# time-shift-r1.net
KiCad netlist of a schematic drawn in EAGLE
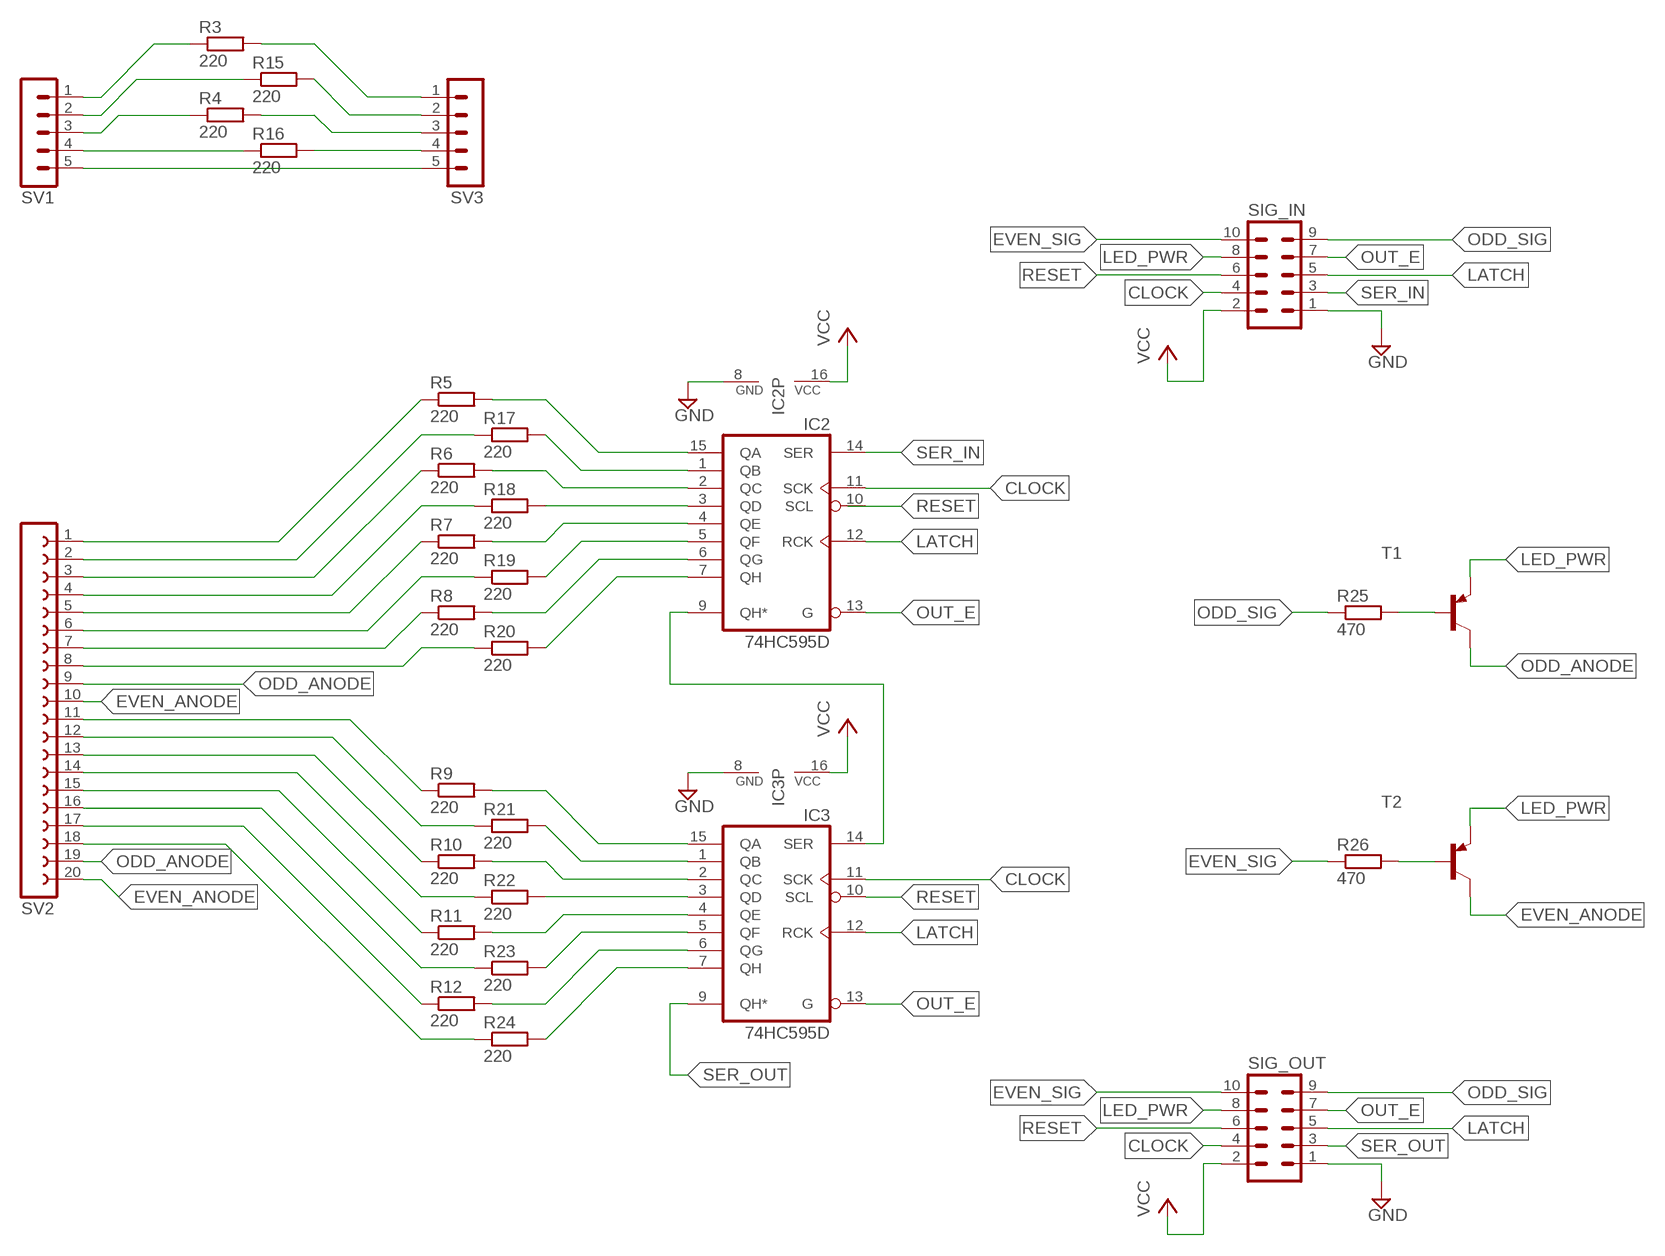
[diagram p0: schematic, sheet 1]

(export (version "E")
  (design (tool "Eeschema 10.0.6"))
  (components
    (comp (ref "IC2")
      (value "74HC595D")
      (footprint "eagle-import:SO16")
      (libsource (lib "eagle-import") (part "74595DHC"))
    )
    (comp (ref "IC3")
      (value "74HC595D")
      (footprint "eagle-import:SO16")
      (libsource (lib "eagle-import") (part "74595DHC"))
    )
    (comp (ref "R3")
      (value "220")
      (footprint "eagle-import:R0805")
      (libsource (lib "eagle-import") (part "R-EU_R0805"))
    )
    (comp (ref "R4")
      (value "220")
      (footprint "eagle-import:R0805")
      (libsource (lib "eagle-import") (part "R-EU_R0805"))
    )
    (comp (ref "R5")
      (value "220")
      (footprint "eagle-import:R0805")
      (libsource (lib "eagle-import") (part "R-EU_R0805"))
    )
    (comp (ref "R6")
      (value "220")
      (footprint "eagle-import:R0805")
      (libsource (lib "eagle-import") (part "R-EU_R0805"))
    )
    (comp (ref "R7")
      (value "220")
      (footprint "eagle-import:R0805")
      (libsource (lib "eagle-import") (part "R-EU_R0805"))
    )
    (comp (ref "R8")
      (value "220")
      (footprint "eagle-import:R0805")
      (libsource (lib "eagle-import") (part "R-EU_R0805"))
    )
    (comp (ref "R9")
      (value "220")
      (footprint "eagle-import:R0805")
      (libsource (lib "eagle-import") (part "R-EU_R0805"))
    )
    (comp (ref "R10")
      (value "220")
      (footprint "eagle-import:R0805")
      (libsource (lib "eagle-import") (part "R-EU_R0805"))
    )
    (comp (ref "R11")
      (value "220")
      (footprint "eagle-import:R0805")
      (libsource (lib "eagle-import") (part "R-EU_R0805"))
    )
    (comp (ref "R12")
      (value "220")
      (footprint "eagle-import:R0805")
      (libsource (lib "eagle-import") (part "R-EU_R0805"))
    )
    (comp (ref "R15")
      (value "220")
      (footprint "eagle-import:R0805")
      (libsource (lib "eagle-import") (part "R-EU_R0805"))
    )
    (comp (ref "R16")
      (value "220")
      (footprint "eagle-import:R0805")
      (libsource (lib "eagle-import") (part "R-EU_R0805"))
    )
    (comp (ref "R17")
      (value "220")
      (footprint "eagle-import:R0805")
      (libsource (lib "eagle-import") (part "R-EU_R0805"))
    )
    (comp (ref "R18")
      (value "220")
      (footprint "eagle-import:R0805")
      (libsource (lib "eagle-import") (part "R-EU_R0805"))
    )
    (comp (ref "R19")
      (value "220")
      (footprint "eagle-import:R0805")
      (libsource (lib "eagle-import") (part "R-EU_R0805"))
    )
    (comp (ref "R20")
      (value "220")
      (footprint "eagle-import:R0805")
      (libsource (lib "eagle-import") (part "R-EU_R0805"))
    )
    (comp (ref "R21")
      (value "220")
      (footprint "eagle-import:R0805")
      (libsource (lib "eagle-import") (part "R-EU_R0805"))
    )
    (comp (ref "R22")
      (value "220")
      (footprint "eagle-import:R0805")
      (libsource (lib "eagle-import") (part "R-EU_R0805"))
    )
    (comp (ref "R23")
      (value "220")
      (footprint "eagle-import:R0805")
      (libsource (lib "eagle-import") (part "R-EU_R0805"))
    )
    (comp (ref "R24")
      (value "220")
      (footprint "eagle-import:R0805")
      (libsource (lib "eagle-import") (part "R-EU_R0805"))
    )
    (comp (ref "R25")
      (value "470")
      (footprint "eagle-import:R0805")
      (libsource (lib "eagle-import") (part "R-EU_R0805"))
    )
    (comp (ref "R26")
      (value "470")
      (footprint "eagle-import:R0805")
      (libsource (lib "eagle-import") (part "R-EU_R0805"))
    )
    (comp (ref "SIG_IN")
      (value "MA05-2")
      (footprint "eagle-import:MA05-2")
      (libsource (lib "eagle-import") (part "MA05-2"))
    )
    (comp (ref "SIG_OUT")
      (value "MA05-2")
      (footprint "eagle-import:MA05-2")
      (libsource (lib "eagle-import") (part "MA05-2"))
    )
    (comp (ref "SV1")
      (value "MA05-1")
      (footprint "eagle-import:MA05-1")
      (libsource (lib "eagle-import") (part "MA05-1"))
    )
    (comp (ref "SV2")
      (value "FE20-1")
      (footprint "eagle-import:FE20")
      (libsource (lib "eagle-import") (part "FE20-1"))
    )
    (comp (ref "SV3")
      (value "MA05-1")
      (footprint "eagle-import:MA05-1")
      (libsource (lib "eagle-import") (part "MA05-1"))
    )
    (comp (ref "T1")
      (value "BC557B-PNP-TO92-EBC")
      (footprint "eagle-import:TO92-EBC")
      (libsource (lib "eagle-import") (part "-PNP-TO92-EBCBC557B"))
    )
    (comp (ref "T2")
      (value "BC557B-PNP-TO92-EBC")
      (footprint "eagle-import:TO92-EBC")
      (libsource (lib "eagle-import") (part "-PNP-TO92-EBCBC557B"))
    )
  )
  (nets
    (net (code "1") (name "CLOCK") (class "Default")
      (node (ref "IC2") (pin "11") (pinfunction "SCK_11") (pintype "input"))
      (node (ref "IC3") (pin "11") (pinfunction "SCK_11") (pintype "input"))
      (node (ref "SIG_IN") (pin "4") (pinfunction "4_4") (pintype "passive"))
      (node (ref "SIG_OUT") (pin "4") (pinfunction "4_4") (pintype "passive"))
    )
    (net (code "2") (name "EVEN_ANODE") (class "Default")
      (node (ref "SV2") (pin "10") (pinfunction "10_10") (pintype "passive"))
      (node (ref "SV2") (pin "20") (pinfunction "20_20") (pintype "passive"))
      (node (ref "T2") (pin "C") (pinfunction "C_C") (pintype "passive"))
    )
    (net (code "3") (name "EVEN_SIG") (class "Default")
      (node (ref "R26") (pin "1") (pinfunction "1_1") (pintype "passive"))
      (node (ref "SIG_IN") (pin "10") (pinfunction "10_10") (pintype "passive"))
      (node (ref "SIG_OUT") (pin "10") (pinfunction "10_10") (pintype "passive"))
    )
    (net (code "4") (name "GND") (class "Default")
      (node (ref "IC2") (pin "8") (pinfunction "GND_8") (pintype "power_in"))
      (node (ref "IC3") (pin "8") (pinfunction "GND_8") (pintype "power_in"))
      (node (ref "SIG_IN") (pin "1") (pinfunction "1_1") (pintype "passive"))
      (node (ref "SIG_OUT") (pin "1") (pinfunction "1_1") (pintype "passive"))
    )
    (net (code "5") (name "LATCH") (class "Default")
      (node (ref "IC2") (pin "12") (pinfunction "RCK_12") (pintype "input"))
      (node (ref "IC3") (pin "12") (pinfunction "RCK_12") (pintype "input"))
      (node (ref "SIG_IN") (pin "5") (pinfunction "5_5") (pintype "passive"))
      (node (ref "SIG_OUT") (pin "5") (pinfunction "5_5") (pintype "passive"))
    )
    (net (code "6") (name "LED_PWR") (class "Default")
      (node (ref "SIG_IN") (pin "8") (pinfunction "8_8") (pintype "passive"))
      (node (ref "SIG_OUT") (pin "8") (pinfunction "8_8") (pintype "passive"))
      (node (ref "T1") (pin "E") (pinfunction "E_E") (pintype "passive"))
      (node (ref "T2") (pin "E") (pinfunction "E_E") (pintype "passive"))
    )
    (net (code "7") (name "Net-(IC2A-QA)") (class "Default")
      (node (ref "IC2") (pin "15") (pinfunction "QA_15") (pintype "tri_state"))
      (node (ref "R5") (pin "2") (pinfunction "2_2") (pintype "passive"))
    )
    (net (code "8") (name "Net-(IC2A-QB)") (class "Default")
      (node (ref "IC2") (pin "1") (pinfunction "QB_1") (pintype "tri_state"))
      (node (ref "R17") (pin "2") (pinfunction "2_2") (pintype "passive"))
    )
    (net (code "9") (name "Net-(IC2A-QC)") (class "Default")
      (node (ref "IC2") (pin "2") (pinfunction "QC_2") (pintype "tri_state"))
      (node (ref "R6") (pin "2") (pinfunction "2_2") (pintype "passive"))
    )
    (net (code "10") (name "Net-(IC2A-QD)") (class "Default")
      (node (ref "IC2") (pin "3") (pinfunction "QD_3") (pintype "tri_state"))
      (node (ref "R18") (pin "2") (pinfunction "2_2") (pintype "passive"))
    )
    (net (code "11") (name "Net-(IC2A-QE)") (class "Default")
      (node (ref "IC2") (pin "4") (pinfunction "QE_4") (pintype "tri_state"))
      (node (ref "R7") (pin "2") (pinfunction "2_2") (pintype "passive"))
    )
    (net (code "12") (name "Net-(IC2A-QF)") (class "Default")
      (node (ref "IC2") (pin "5") (pinfunction "QF_5") (pintype "tri_state"))
      (node (ref "R19") (pin "2") (pinfunction "2_2") (pintype "passive"))
    )
    (net (code "13") (name "Net-(IC2A-QG)") (class "Default")
      (node (ref "IC2") (pin "6") (pinfunction "QG_6") (pintype "tri_state"))
      (node (ref "R8") (pin "2") (pinfunction "2_2") (pintype "passive"))
    )
    (net (code "14") (name "Net-(IC2A-QH)") (class "Default")
      (node (ref "IC2") (pin "7") (pinfunction "QH_7") (pintype "tri_state"))
      (node (ref "R20") (pin "2") (pinfunction "2_2") (pintype "passive"))
    )
    (net (code "15") (name "Net-(IC2A-QH*)") (class "Default")
      (node (ref "IC2") (pin "9") (pinfunction "QH*_9") (pintype "tri_state"))
      (node (ref "IC3") (pin "14") (pinfunction "SER_14") (pintype "input"))
    )
    (net (code "16") (name "Net-(IC3A-QA)") (class "Default")
      (node (ref "IC3") (pin "15") (pinfunction "QA_15") (pintype "tri_state"))
      (node (ref "R9") (pin "2") (pinfunction "2_2") (pintype "passive"))
    )
    (net (code "17") (name "Net-(IC3A-QB)") (class "Default")
      (node (ref "IC3") (pin "1") (pinfunction "QB_1") (pintype "tri_state"))
      (node (ref "R21") (pin "2") (pinfunction "2_2") (pintype "passive"))
    )
    (net (code "18") (name "Net-(IC3A-QC)") (class "Default")
      (node (ref "IC3") (pin "2") (pinfunction "QC_2") (pintype "tri_state"))
      (node (ref "R10") (pin "2") (pinfunction "2_2") (pintype "passive"))
    )
    (net (code "19") (name "Net-(IC3A-QD)") (class "Default")
      (node (ref "IC3") (pin "3") (pinfunction "QD_3") (pintype "tri_state"))
      (node (ref "R22") (pin "2") (pinfunction "2_2") (pintype "passive"))
    )
    (net (code "20") (name "Net-(IC3A-QE)") (class "Default")
      (node (ref "IC3") (pin "4") (pinfunction "QE_4") (pintype "tri_state"))
      (node (ref "R11") (pin "2") (pinfunction "2_2") (pintype "passive"))
    )
    (net (code "21") (name "Net-(IC3A-QF)") (class "Default")
      (node (ref "IC3") (pin "5") (pinfunction "QF_5") (pintype "tri_state"))
      (node (ref "R23") (pin "2") (pinfunction "2_2") (pintype "passive"))
    )
    (net (code "22") (name "Net-(IC3A-QG)") (class "Default")
      (node (ref "IC3") (pin "6") (pinfunction "QG_6") (pintype "tri_state"))
      (node (ref "R12") (pin "2") (pinfunction "2_2") (pintype "passive"))
    )
    (net (code "23") (name "Net-(IC3A-QH)") (class "Default")
      (node (ref "IC3") (pin "7") (pinfunction "QH_7") (pintype "tri_state"))
      (node (ref "R24") (pin "2") (pinfunction "2_2") (pintype "passive"))
    )
    (net (code "24") (name "Net-(R3-Pad1)") (class "Default")
      (node (ref "R3") (pin "1") (pinfunction "1_1") (pintype "passive"))
      (node (ref "SV1") (pin "1") (pinfunction "1_1") (pintype "passive"))
    )
    (net (code "25") (name "Net-(R3-Pad2)") (class "Default")
      (node (ref "R3") (pin "2") (pinfunction "2_2") (pintype "passive"))
      (node (ref "SV3") (pin "1") (pinfunction "1_1") (pintype "passive"))
    )
    (net (code "26") (name "Net-(R4-Pad1)") (class "Default")
      (node (ref "R4") (pin "1") (pinfunction "1_1") (pintype "passive"))
      (node (ref "SV1") (pin "3") (pinfunction "3_3") (pintype "passive"))
    )
    (net (code "27") (name "Net-(R4-Pad2)") (class "Default")
      (node (ref "R4") (pin "2") (pinfunction "2_2") (pintype "passive"))
      (node (ref "SV3") (pin "3") (pinfunction "3_3") (pintype "passive"))
    )
    (net (code "28") (name "Net-(R5-Pad1)") (class "Default")
      (node (ref "R5") (pin "1") (pinfunction "1_1") (pintype "passive"))
      (node (ref "SV2") (pin "1") (pinfunction "1_1") (pintype "passive"))
    )
    (net (code "29") (name "Net-(R6-Pad1)") (class "Default")
      (node (ref "R6") (pin "1") (pinfunction "1_1") (pintype "passive"))
      (node (ref "SV2") (pin "3") (pinfunction "3_3") (pintype "passive"))
    )
    (net (code "30") (name "Net-(R7-Pad1)") (class "Default")
      (node (ref "R7") (pin "1") (pinfunction "1_1") (pintype "passive"))
      (node (ref "SV2") (pin "5") (pinfunction "5_5") (pintype "passive"))
    )
    (net (code "31") (name "Net-(R8-Pad1)") (class "Default")
      (node (ref "R8") (pin "1") (pinfunction "1_1") (pintype "passive"))
      (node (ref "SV2") (pin "7") (pinfunction "7_7") (pintype "passive"))
    )
    (net (code "32") (name "Net-(R9-Pad1)") (class "Default")
      (node (ref "R9") (pin "1") (pinfunction "1_1") (pintype "passive"))
      (node (ref "SV2") (pin "11") (pinfunction "11_11") (pintype "passive"))
    )
    (net (code "33") (name "Net-(R10-Pad1)") (class "Default")
      (node (ref "R10") (pin "1") (pinfunction "1_1") (pintype "passive"))
      (node (ref "SV2") (pin "13") (pinfunction "13_13") (pintype "passive"))
    )
    (net (code "34") (name "Net-(R11-Pad1)") (class "Default")
      (node (ref "R11") (pin "1") (pinfunction "1_1") (pintype "passive"))
      (node (ref "SV2") (pin "15") (pinfunction "15_15") (pintype "passive"))
    )
    (net (code "35") (name "Net-(R12-Pad1)") (class "Default")
      (node (ref "R12") (pin "1") (pinfunction "1_1") (pintype "passive"))
      (node (ref "SV2") (pin "17") (pinfunction "17_17") (pintype "passive"))
    )
    (net (code "36") (name "Net-(R15-Pad1)") (class "Default")
      (node (ref "R15") (pin "1") (pinfunction "1_1") (pintype "passive"))
      (node (ref "SV1") (pin "2") (pinfunction "2_2") (pintype "passive"))
    )
    (net (code "37") (name "Net-(R15-Pad2)") (class "Default")
      (node (ref "R15") (pin "2") (pinfunction "2_2") (pintype "passive"))
      (node (ref "SV3") (pin "2") (pinfunction "2_2") (pintype "passive"))
    )
    (net (code "38") (name "Net-(R16-Pad1)") (class "Default")
      (node (ref "R16") (pin "1") (pinfunction "1_1") (pintype "passive"))
      (node (ref "SV1") (pin "4") (pinfunction "4_4") (pintype "passive"))
    )
    (net (code "39") (name "Net-(R16-Pad2)") (class "Default")
      (node (ref "R16") (pin "2") (pinfunction "2_2") (pintype "passive"))
      (node (ref "SV3") (pin "4") (pinfunction "4_4") (pintype "passive"))
    )
    (net (code "40") (name "Net-(R17-Pad1)") (class "Default")
      (node (ref "R17") (pin "1") (pinfunction "1_1") (pintype "passive"))
      (node (ref "SV2") (pin "2") (pinfunction "2_2") (pintype "passive"))
    )
    (net (code "41") (name "Net-(R18-Pad1)") (class "Default")
      (node (ref "R18") (pin "1") (pinfunction "1_1") (pintype "passive"))
      (node (ref "SV2") (pin "4") (pinfunction "4_4") (pintype "passive"))
    )
    (net (code "42") (name "Net-(R19-Pad1)") (class "Default")
      (node (ref "R19") (pin "1") (pinfunction "1_1") (pintype "passive"))
      (node (ref "SV2") (pin "6") (pinfunction "6_6") (pintype "passive"))
    )
    (net (code "43") (name "Net-(R20-Pad1)") (class "Default")
      (node (ref "R20") (pin "1") (pinfunction "1_1") (pintype "passive"))
      (node (ref "SV2") (pin "8") (pinfunction "8_8") (pintype "passive"))
    )
    (net (code "44") (name "Net-(R21-Pad1)") (class "Default")
      (node (ref "R21") (pin "1") (pinfunction "1_1") (pintype "passive"))
      (node (ref "SV2") (pin "12") (pinfunction "12_12") (pintype "passive"))
    )
    (net (code "45") (name "Net-(R22-Pad1)") (class "Default")
      (node (ref "R22") (pin "1") (pinfunction "1_1") (pintype "passive"))
      (node (ref "SV2") (pin "14") (pinfunction "14_14") (pintype "passive"))
    )
    (net (code "46") (name "Net-(R23-Pad1)") (class "Default")
      (node (ref "R23") (pin "1") (pinfunction "1_1") (pintype "passive"))
      (node (ref "SV2") (pin "16") (pinfunction "16_16") (pintype "passive"))
    )
    (net (code "47") (name "Net-(R24-Pad1)") (class "Default")
      (node (ref "R24") (pin "1") (pinfunction "1_1") (pintype "passive"))
      (node (ref "SV2") (pin "18") (pinfunction "18_18") (pintype "passive"))
    )
    (net (code "48") (name "Net-(R25-Pad2)") (class "Default")
      (node (ref "R25") (pin "2") (pinfunction "2_2") (pintype "passive"))
      (node (ref "T1") (pin "B") (pinfunction "B_B") (pintype "passive"))
    )
    (net (code "49") (name "Net-(R26-Pad2)") (class "Default")
      (node (ref "R26") (pin "2") (pinfunction "2_2") (pintype "passive"))
      (node (ref "T2") (pin "B") (pinfunction "B_B") (pintype "passive"))
    )
    (net (code "50") (name "Net-(SV1-Pad5)") (class "Default")
      (node (ref "SV1") (pin "5") (pinfunction "5_5") (pintype "passive"))
      (node (ref "SV3") (pin "5") (pinfunction "5_5") (pintype "passive"))
    )
    (net (code "51") (name "ODD_ANODE") (class "Default")
      (node (ref "SV2") (pin "19") (pinfunction "19_19") (pintype "passive"))
      (node (ref "SV2") (pin "9") (pinfunction "9_9") (pintype "passive"))
      (node (ref "T1") (pin "C") (pinfunction "C_C") (pintype "passive"))
    )
    (net (code "52") (name "ODD_SIG") (class "Default")
      (node (ref "R25") (pin "1") (pinfunction "1_1") (pintype "passive"))
      (node (ref "SIG_IN") (pin "9") (pinfunction "9_9") (pintype "passive"))
      (node (ref "SIG_OUT") (pin "9") (pinfunction "9_9") (pintype "passive"))
    )
    (net (code "53") (name "OUT_E") (class "Default")
      (node (ref "IC2") (pin "13") (pinfunction "G_13") (pintype "input"))
      (node (ref "IC3") (pin "13") (pinfunction "G_13") (pintype "input"))
      (node (ref "SIG_IN") (pin "7") (pinfunction "7_7") (pintype "passive"))
      (node (ref "SIG_OUT") (pin "7") (pinfunction "7_7") (pintype "passive"))
    )
    (net (code "54") (name "RESET") (class "Default")
      (node (ref "IC3") (pin "10") (pinfunction "SCL_10") (pintype "input"))
      (node (ref "SIG_IN") (pin "6") (pinfunction "6_6") (pintype "passive"))
      (node (ref "SIG_OUT") (pin "6") (pinfunction "6_6") (pintype "passive"))
    )
    (net (code "55") (name "SER_IN") (class "Default")
      (node (ref "IC2") (pin "14") (pinfunction "SER_14") (pintype "input"))
      (node (ref "SIG_IN") (pin "3") (pinfunction "3_3") (pintype "passive"))
    )
    (net (code "56") (name "SER_OUT") (class "Default")
      (node (ref "IC3") (pin "9") (pinfunction "QH*_9") (pintype "tri_state"))
      (node (ref "SIG_OUT") (pin "3") (pinfunction "3_3") (pintype "passive"))
    )
    (net (code "57") (name "VCC") (class "Default")
      (node (ref "IC2") (pin "16") (pinfunction "VCC_16") (pintype "power_in"))
      (node (ref "IC3") (pin "16") (pinfunction "VCC_16") (pintype "power_in"))
      (node (ref "SIG_IN") (pin "2") (pinfunction "2_2") (pintype "passive"))
      (node (ref "SIG_OUT") (pin "2") (pinfunction "2_2") (pintype "passive"))
    )
    (net (code "58") (name "unconnected-(IC2A-SCL-Pad10)") (class "Default")
      (node (ref "IC2") (pin "10") (pinfunction "SCL_10") (pintype "input"))
    )
  )
)
